# Module.net
KiCad netlist of a schematic drawn in EAGLE
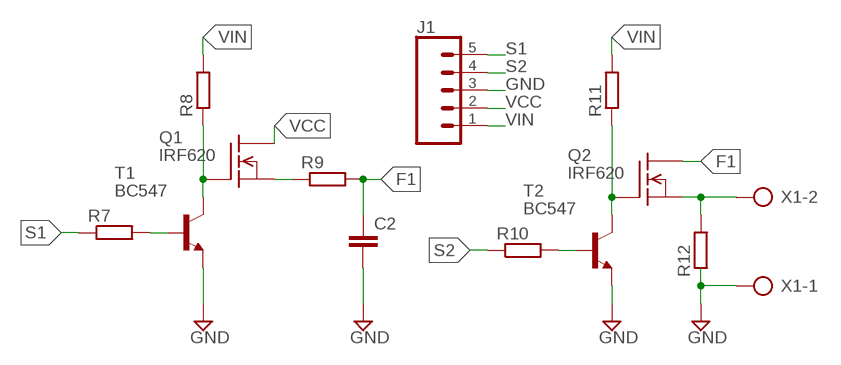
[diagram p0: schematic, sheet 1]

(export (version "E")
  (design (tool "Eeschema 10.0.6"))
  (components
    (comp (ref "C2")
      (value "C5/5")
      (footprint "eagle-import:C5B5")
      (libsource (lib "eagle-import") (part "C5/5"))
    )
    (comp (ref "J1")
      (value "CONN_05")
      (footprint "eagle-import:1X05")
      (libsource (lib "eagle-import") (part "CONN_05"))
    )
    (comp (ref "Q1")
      (value "IRF620")
      (footprint "eagle-import:TO220")
      (libsource (lib "eagle-import") (part "IRF620"))
    )
    (comp (ref "Q2")
      (value "IRF620")
      (footprint "eagle-import:TO220")
      (libsource (lib "eagle-import") (part "IRF620"))
    )
    (comp (ref "R7")
      (value "R-EU_0309/12")
      (footprint "eagle-import:0309_12")
      (libsource (lib "eagle-import") (part "R-EU_0309/12"))
    )
    (comp (ref "R8")
      (value "R-EU_0309/12")
      (footprint "eagle-import:0309_12")
      (libsource (lib "eagle-import") (part "R-EU_0309/12"))
    )
    (comp (ref "R9")
      (value "R-EU_0309/12")
      (footprint "eagle-import:0309_12")
      (libsource (lib "eagle-import") (part "R-EU_0309/12"))
    )
    (comp (ref "R10")
      (value "R-EU_0309/12")
      (footprint "eagle-import:0309_12")
      (libsource (lib "eagle-import") (part "R-EU_0309/12"))
    )
    (comp (ref "R11")
      (value "R-EU_0309/12")
      (footprint "eagle-import:0309_12")
      (libsource (lib "eagle-import") (part "R-EU_0309/12"))
    )
    (comp (ref "R12")
      (value "R-EU_0309/12")
      (footprint "eagle-import:0309_12")
      (libsource (lib "eagle-import") (part "R-EU_0309/12"))
    )
    (comp (ref "T1")
      (value "BC547")
      (footprint "eagle-import:TO92")
      (libsource (lib "eagle-import") (part "BC547"))
    )
    (comp (ref "T2")
      (value "BC547")
      (footprint "eagle-import:TO92")
      (libsource (lib "eagle-import") (part "BC547"))
    )
    (comp (ref "X1")
      (value "AK500/2-H")
      (footprint "eagle-import:AK500_2-H")
      (libsource (lib "eagle-import") (part "AK500/2-H"))
    )
  )
  (nets
    (net (code "1") (name "F1") (class "Default")
      (node (ref "C2") (pin "1") (pinfunction "1_1") (pintype "passive"))
      (node (ref "Q2") (pin "2") (pinfunction "D_2") (pintype "passive"))
      (node (ref "R9") (pin "2") (pinfunction "2_2") (pintype "passive"))
    )
    (net (code "2") (name "GND") (class "Default")
      (node (ref "C2") (pin "2") (pinfunction "2_2") (pintype "passive"))
      (node (ref "J1") (pin "3") (pinfunction "3_3") (pintype "passive"))
      (node (ref "R12") (pin "1") (pinfunction "1_1") (pintype "passive"))
      (node (ref "T1") (pin "1") (pinfunction "E_1") (pintype "passive"))
      (node (ref "T2") (pin "1") (pinfunction "E_1") (pintype "passive"))
      (node (ref "X1") (pin "1") (pinfunction "KL_1") (pintype "passive"))
    )
    (net (code "3") (name "Net-(Q1-G)") (class "Default")
      (node (ref "Q1") (pin "1") (pinfunction "G_1") (pintype "passive"))
      (node (ref "R8") (pin "1") (pinfunction "1_1") (pintype "passive"))
      (node (ref "T1") (pin "3") (pinfunction "C_3") (pintype "passive"))
    )
    (net (code "4") (name "Net-(Q1-S)") (class "Default")
      (node (ref "Q1") (pin "3") (pinfunction "S_3") (pintype "passive"))
      (node (ref "R9") (pin "1") (pinfunction "1_1") (pintype "passive"))
    )
    (net (code "5") (name "Net-(Q2-G)") (class "Default")
      (node (ref "Q2") (pin "1") (pinfunction "G_1") (pintype "passive"))
      (node (ref "R11") (pin "1") (pinfunction "1_1") (pintype "passive"))
      (node (ref "T2") (pin "3") (pinfunction "C_3") (pintype "passive"))
    )
    (net (code "6") (name "Net-(Q2-S)") (class "Default")
      (node (ref "Q2") (pin "3") (pinfunction "S_3") (pintype "passive"))
      (node (ref "R12") (pin "2") (pinfunction "2_2") (pintype "passive"))
      (node (ref "X1") (pin "2") (pinfunction "KL_2") (pintype "passive"))
    )
    (net (code "7") (name "Net-(T1-B)") (class "Default")
      (node (ref "R7") (pin "2") (pinfunction "2_2") (pintype "passive"))
      (node (ref "T1") (pin "2") (pinfunction "B_2") (pintype "passive"))
    )
    (net (code "8") (name "Net-(T2-B)") (class "Default")
      (node (ref "R10") (pin "2") (pinfunction "2_2") (pintype "passive"))
      (node (ref "T2") (pin "2") (pinfunction "B_2") (pintype "passive"))
    )
    (net (code "9") (name "S1") (class "Default")
      (node (ref "J1") (pin "5") (pinfunction "5_5") (pintype "passive"))
      (node (ref "R7") (pin "1") (pinfunction "1_1") (pintype "passive"))
    )
    (net (code "10") (name "S2") (class "Default")
      (node (ref "J1") (pin "4") (pinfunction "4_4") (pintype "passive"))
      (node (ref "R10") (pin "1") (pinfunction "1_1") (pintype "passive"))
    )
    (net (code "11") (name "VCC") (class "Default")
      (node (ref "J1") (pin "2") (pinfunction "2_2") (pintype "passive"))
      (node (ref "Q1") (pin "2") (pinfunction "D_2") (pintype "passive"))
    )
    (net (code "12") (name "VIN") (class "Default")
      (node (ref "J1") (pin "1") (pinfunction "1_1") (pintype "passive"))
      (node (ref "R11") (pin "2") (pinfunction "2_2") (pintype "passive"))
      (node (ref "R8") (pin "2") (pinfunction "2_2") (pintype "passive"))
    )
  )
)
